# ReceiverBlock.net
KiCad netlist of a schematic drawn in Altium Designer
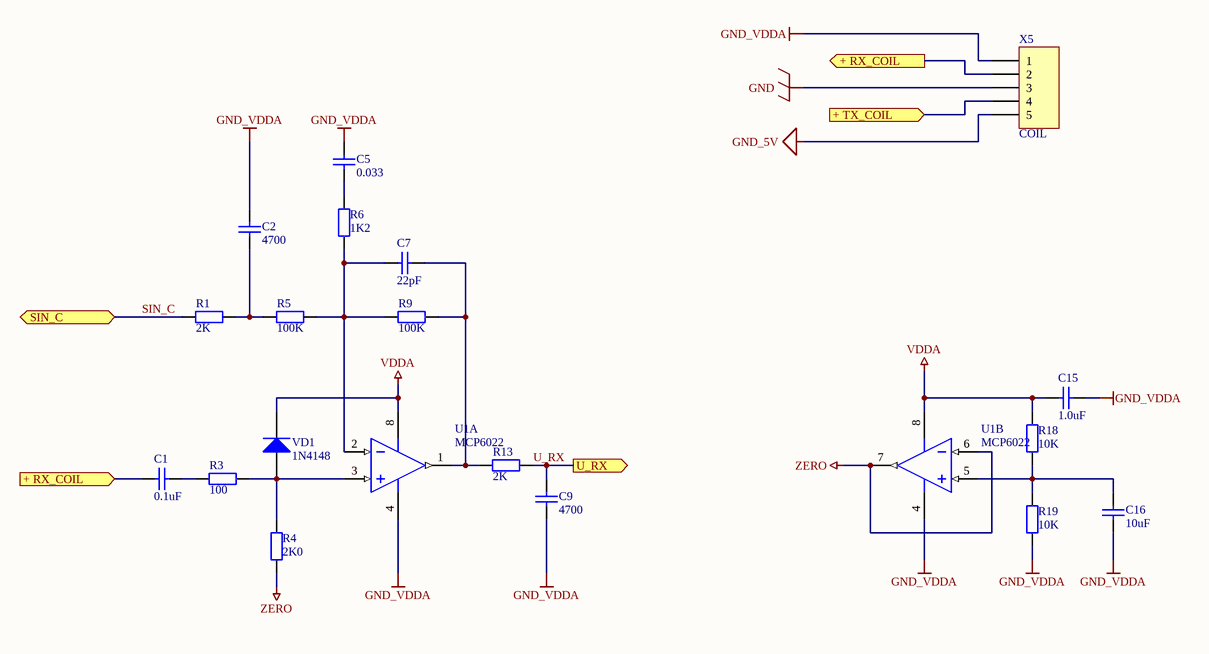
[diagram p0: ReceiverBlock.SchDoc]

(export (version "E")
  (design (tool "Eeschema 10.0.6"))
  (components
    (comp (ref "C1")
      (value "0.1uF")
      (footprint "1206_SMD_Capacitor")
      (description "Capacitor")
      (fields (field (name "PUBLISHER") "Altium Limited"))
      (libsource (lib "Quasar ARM") (part "Capacitor SMD"))
    )
    (comp (ref "C2")
      (value "4700")
      (footprint "1206_SMD_Capacitor")
      (description "Capacitor")
      (fields (field (name "PUBLISHER") "Altium Limited"))
      (libsource (lib "Quasar ARM") (part "Capacitor SMD"))
    )
    (comp (ref "C5")
      (value "0.033")
      (footprint "1206_SMD_Capacitor")
      (description "Capacitor")
      (fields (field (name "PUBLISHER") "Altium Limited"))
      (libsource (lib "Quasar ARM") (part "Capacitor SMD"))
    )
    (comp (ref "C7")
      (value "22pF")
      (footprint "1206_SMD_Capacitor")
      (description "Capacitor")
      (fields (field (name "PUBLISHER") "Altium Limited"))
      (libsource (lib "Quasar ARM") (part "Capacitor SMD"))
    )
    (comp (ref "C9")
      (value "4700")
      (footprint "1206_SMD_Capacitor")
      (description "Capacitor")
      (fields (field (name "PUBLISHER") "Altium Limited"))
      (libsource (lib "Quasar ARM") (part "Capacitor SMD"))
    )
    (comp (ref "C15")
      (value "1.0uF")
      (footprint "1206_SMD_Capacitor")
      (description "Capacitor")
      (fields (field (name "PUBLISHER") "Altium Limited"))
      (libsource (lib "Quasar ARM") (part "Capacitor SMD"))
    )
    (comp (ref "C16")
      (value "10uF")
      (footprint "1206_SMD_Capacitor")
      (description "Capacitor")
      (fields (field (name "PUBLISHER") "Altium Limited"))
      (libsource (lib "Quasar ARM") (part "Capacitor SMD"))
    )
    (comp (ref "R1")
      (value "2K")
      (footprint "1206_SMD_Resistor")
      (description "Resistor")
      (fields (field (name "PUBLISHER") "Altium Limited"))
      (libsource (lib "") (part "Resistor_2"))
    )
    (comp (ref "R3")
      (value "100")
      (footprint "1206_SMD_Resistor")
      (description "Resistor")
      (fields (field (name "PUBLISHER") "Dmitry Kuzmin"))
      (libsource (lib "") (part "Resistor_3"))
    )
    (comp (ref "R4")
      (value "2K0")
      (footprint "1206_SMD_Resistor")
      (description "Resistor")
      (fields (field (name "PUBLISHER") "Altium Limited"))
      (libsource (lib "") (part "Resistor_1"))
    )
    (comp (ref "R5")
      (value "100K")
      (footprint "1206_SMD_Resistor")
      (description "Resistor")
      (fields (field (name "PUBLISHER") "Dmitry Kuzmin"))
      (libsource (lib "") (part "Resistor_2"))
    )
    (comp (ref "R6")
      (value "1K2")
      (footprint "1206_SMD_Resistor")
      (description "Resistor")
      (fields (field (name "PUBLISHER") "Dmitry Kuzmin"))
      (libsource (lib "Quasar ARM") (part "Resistor"))
    )
    (comp (ref "R9")
      (value "100K")
      (footprint "1206_SMD_Resistor")
      (description "Resistor")
      (fields (field (name "PUBLISHER") "Dmitry Kuzmin"))
      (libsource (lib "") (part "Resistor_2"))
    )
    (comp (ref "R13")
      (value "2K")
      (footprint "1206_SMD_Resistor")
      (description "Resistor")
      (fields (field (name "PUBLISHER") "Dmitry Kuzmin"))
      (libsource (lib "") (part "Resistor_2"))
    )
    (comp (ref "R18")
      (value "10K")
      (footprint "1206_SMD_Resistor")
      (description "Resistor")
      (fields (field (name "PUBLISHER") "Dmitry Kuzmin"))
      (libsource (lib "Quasar ARM") (part "Resistor"))
    )
    (comp (ref "R19")
      (value "10K")
      (footprint "1206_SMD_Resistor")
      (description "Resistor")
      (fields (field (name "PUBLISHER") "Dmitry Kuzmin"))
      (libsource (lib "Quasar ARM") (part "Resistor"))
    )
    (comp (ref "U1")
      (value "MCP6022")
      (footprint "SOIC-SN8_N")
      (description "Rail-to-Rail Input/Output, 10 MHz Operational Amplifier, 8-Pin SOIC, Industrial Temperature")
      (fields (field (name "PUBLISHER") "Altium Limited"))
      (libsource (lib "Quasar ARM") (part "MCP6022-I/SN"))
    )
    (comp (ref "VD1")
      (value "1N4148")
      (footprint "SOD-323")
      (description "High Conductance Fast Diode")
      (fields (field (name "PUBLISHER") "Altium Limited"))
      (libsource (lib "Quasar ARM") (part "1N4148"))
    )
    (comp (ref "X5")
      (value "COIL")
      (footprint "GX16-5")
      (description "Jack, 5 pin")
      (fields (field (name "PUBLISHER") "Altium Limited"))
      (libsource (lib "Quasar ARM") (part "Jack 5p"))
    )
  )
  (nets
    (net (code "1") (name "/+ RX_COIL") (class "Default")
      (node (ref "C1") (pin "1") (pinfunction "1_1") (pintype "passive"))
      (node (ref "X5") (pin "2") (pinfunction "2_2") (pintype "passive"))
    )
    (net (code "2") (name "/+ TX_COIL") (class "Default")
      (node (ref "X5") (pin "4") (pinfunction "4_4") (pintype "passive"))
    )
    (net (code "3") (name "/SIN_C") (class "Default")
      (node (ref "R1") (pin "1") (pinfunction "1_1") (pintype "passive"))
    )
    (net (code "4") (name "/U_RX") (class "Default")
      (node (ref "C9") (pin "2") (pinfunction "2_2") (pintype "passive"))
      (node (ref "R13") (pin "2") (pinfunction "2_2") (pintype "passive"))
    )
    (net (code "5") (name "GND") (class "Default")
      (node (ref "X5") (pin "3") (pinfunction "3_3") (pintype "passive"))
    )
    (net (code "6") (name "GND_5V") (class "Default")
      (node (ref "X5") (pin "5") (pinfunction "5_5") (pintype "passive"))
    )
    (net (code "7") (name "GND_VDDA") (class "Default")
      (node (ref "C15") (pin "2") (pinfunction "2_2") (pintype "passive"))
      (node (ref "C16") (pin "1") (pinfunction "1_1") (pintype "passive"))
      (node (ref "C2") (pin "1") (pinfunction "1_1") (pintype "passive"))
      (node (ref "C5") (pin "2") (pinfunction "2_2") (pintype "passive"))
      (node (ref "C9") (pin "1") (pinfunction "1_1") (pintype "passive"))
      (node (ref "R19") (pin "1") (pinfunction "1_1") (pintype "passive"))
      (node (ref "U1") (pin "4") (pinfunction "VSS_4") (pintype "power_in"))
      (node (ref "X5") (pin "1") (pinfunction "1_1") (pintype "passive"))
    )
    (net (code "8") (name "Net-(C1-Pad2)") (class "Default")
      (node (ref "C1") (pin "2") (pinfunction "2_2") (pintype "passive"))
      (node (ref "R3") (pin "2") (pinfunction "2_2") (pintype "passive"))
    )
    (net (code "9") (name "Net-(C2-Pad2)") (class "Default")
      (node (ref "C2") (pin "2") (pinfunction "2_2") (pintype "passive"))
      (node (ref "R1") (pin "2") (pinfunction "2_2") (pintype "passive"))
      (node (ref "R5") (pin "1") (pinfunction "1_1") (pintype "passive"))
    )
    (net (code "10") (name "Net-(C5-Pad1)") (class "Default")
      (node (ref "C5") (pin "1") (pinfunction "1_1") (pintype "passive"))
      (node (ref "R6") (pin "2") (pinfunction "2_2") (pintype "passive"))
    )
    (net (code "11") (name "Net-(U1A-VINA+)") (class "Default")
      (node (ref "R3") (pin "1") (pinfunction "1_1") (pintype "passive"))
      (node (ref "R4") (pin "1") (pinfunction "1_1") (pintype "passive"))
      (node (ref "U1") (pin "3") (pinfunction "VINA+_3") (pintype "input"))
      (node (ref "VD1") (pin "1") (pinfunction "A_1") (pintype "passive"))
    )
    (net (code "12") (name "Net-(U1A-VINA-)") (class "Default")
      (node (ref "C7") (pin "2") (pinfunction "2_2") (pintype "passive"))
      (node (ref "R5") (pin "2") (pinfunction "2_2") (pintype "passive"))
      (node (ref "R6") (pin "1") (pinfunction "1_1") (pintype "passive"))
      (node (ref "R9") (pin "1") (pinfunction "1_1") (pintype "passive"))
      (node (ref "U1") (pin "2") (pinfunction "VINA-_2") (pintype "input"))
    )
    (net (code "13") (name "Net-(U1A-VOUTA)") (class "Default")
      (node (ref "C7") (pin "1") (pinfunction "1_1") (pintype "passive"))
      (node (ref "R13") (pin "1") (pinfunction "1_1") (pintype "passive"))
      (node (ref "R9") (pin "2") (pinfunction "2_2") (pintype "passive"))
      (node (ref "U1") (pin "1") (pinfunction "VOUTA_1") (pintype "output"))
    )
    (net (code "14") (name "Net-(U1B-VINB+)") (class "Default")
      (node (ref "C16") (pin "2") (pinfunction "2_2") (pintype "passive"))
      (node (ref "R18") (pin "1") (pinfunction "1_1") (pintype "passive"))
      (node (ref "R19") (pin "2") (pinfunction "2_2") (pintype "passive"))
      (node (ref "U1") (pin "5") (pinfunction "VINB+_5") (pintype "input"))
    )
    (net (code "15") (name "VDDA") (class "Default")
      (node (ref "C15") (pin "1") (pinfunction "1_1") (pintype "passive"))
      (node (ref "R18") (pin "2") (pinfunction "2_2") (pintype "passive"))
      (node (ref "U1") (pin "8") (pinfunction "VDD_8") (pintype "power_in"))
      (node (ref "VD1") (pin "2") (pinfunction "K_2") (pintype "passive"))
    )
    (net (code "16") (name "ZERO") (class "Default")
      (node (ref "R4") (pin "2") (pinfunction "2_2") (pintype "passive"))
      (node (ref "U1") (pin "6") (pinfunction "VINB-_6") (pintype "input"))
      (node (ref "U1") (pin "7") (pinfunction "VOUTB_7") (pintype "output"))
    )
  )
)
